# power.net
KiCad netlist of a schematic drawn in Altium Designer
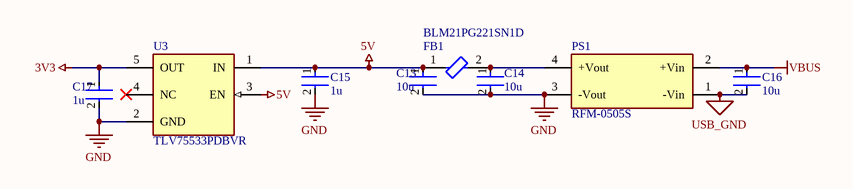
[diagram p0: power.SchDoc]

(export (version "E")
  (design (tool "Eeschema 10.0.6"))
  (components
    (comp (ref "C13")
      (value "10u")
      (footprint "C_IM 0603")
      (description "Multilayer Ceramic Capacitors MLCC – SMD/SMT; YAGEO; CC0603MRX5R7BB106; 10 µF; 0603; 16 V; 16 V")
      (fields
        (field (name "MANUFACTURER") "Yageo Group")
        (field (name "MANUFACTURER PART NUMBER") "CC0603MRX5R7BB106")
      )
      (libsource (lib "Schlib1") (part "CC0603MRX5R7BB106"))
    )
    (comp (ref "C14")
      (value "10u")
      (footprint "C_IM 0603")
      (description "Multilayer Ceramic Capacitors MLCC – SMD/SMT; YAGEO; CC0603MRX5R7BB106; 10 µF; 0603; 16 V; 16 V")
      (fields
        (field (name "MANUFACTURER") "Yageo Group")
        (field (name "MANUFACTURER PART NUMBER") "CC0603MRX5R7BB106")
      )
      (libsource (lib "Schlib1") (part "CC0603MRX5R7BB106"))
    )
    (comp (ref "C15")
      (value "1u")
      (footprint "C_IM 0603")
      (description "16V 1uF X7R ±10% 0603 Multilayer Ceramic Capacitors MLCC - SMD/SMT ROHS")
      (fields
        (field (name "MANUFACTURER") "Yageo Group")
        (field (name "MANUFACTURER PART NUMBER") "CC0603KRX7R7BB105")
      )
      (libsource (lib "Schlib1") (part "CC0603KRX7R7BB105"))
    )
    (comp (ref "C16")
      (value "10u")
      (footprint "C_IM 0603")
      (description "Multilayer Ceramic Capacitors MLCC – SMD/SMT; YAGEO; CC0603MRX5R7BB106; 10 µF; 0603; 16 V; 16 V")
      (fields
        (field (name "MANUFACTURER") "Yageo Group")
        (field (name "MANUFACTURER PART NUMBER") "CC0603MRX5R7BB106")
      )
      (libsource (lib "Schlib1") (part "CC0603MRX5R7BB106"))
    )
    (comp (ref "C17")
      (value "1u")
      (footprint "C_IM 0603")
      (description "16V 1uF X7R ±10% 0603 Multilayer Ceramic Capacitors MLCC - SMD/SMT ROHS")
      (fields
        (field (name "MANUFACTURER") "Yageo Group")
        (field (name "MANUFACTURER PART NUMBER") "CC0603KRX7R7BB105")
      )
      (libsource (lib "Schlib1") (part "CC0603KRX7R7BB105"))
    )
    (comp (ref "FB1")
      (value "BLM21PG221SN1D")
      (footprint "FB_IM 0805")
      (description "Ferrite Beads Multi-Layer 220Ohm 25% 100MHz 2A 45mOhm DCR 0805 Paper T/R")
      (fields (field (name "MANUFACTURER") "Murata") (field (name "TOLERANCE") "25%"))
      (libsource (lib "high_voltage_controller") (part "BLM21PG221SN1D"))
    )
    (comp (ref "PS1")
      (value "RFM-0505S")
      (footprint "4-SIP")
      (description "DC DC CONVERTER 5V 1W / Isolated Module DC DC Converter 1 Output 5V 200mA - 5V Input")
      (fields (field (name "MANUFACTURER") "Recom Power"))
      (libsource (lib "Schlib1") (part "RFM-0505S"))
    )
    (comp (ref "U3")
      (value "TLV75533PDBVR")
      (footprint "SOT-23-5")
      (description "500mA high-PSRR low-IQ low-dropout voltage regulator with enable 5-SOT-23 -40 to 125")
      (fields (field (name "MANUFACTURER") "Texas Instruments"))
      (libsource (lib "high_voltage_controller") (part "TLV75533PDBVR"))
    )
  )
  (nets
    (net (code "1") (name "3V3") (class "Default")
      (node (ref "C17") (pin "1") (pinfunction "1_1") (pintype "passive"))
      (node (ref "U3") (pin "5") (pinfunction "OUT_5") (pintype "power_in"))
    )
    (net (code "2") (name "5V") (class "Default")
      (node (ref "C13") (pin "1") (pinfunction "1_1") (pintype "passive"))
      (node (ref "C15") (pin "1") (pinfunction "1_1") (pintype "passive"))
      (node (ref "FB1") (pin "1") (pinfunction "1_1") (pintype "passive"))
      (node (ref "U3") (pin "1") (pinfunction "IN_1") (pintype "power_in"))
      (node (ref "U3") (pin "3") (pinfunction "EN_3") (pintype "input"))
    )
    (net (code "3") (name "GND") (class "Default")
      (node (ref "C13") (pin "2") (pinfunction "2_2") (pintype "passive"))
      (node (ref "C14") (pin "2") (pinfunction "2_2") (pintype "passive"))
      (node (ref "C15") (pin "2") (pinfunction "2_2") (pintype "passive"))
      (node (ref "C17") (pin "2") (pinfunction "2_2") (pintype "passive"))
      (node (ref "PS1") (pin "3") (pinfunction "-Vout_3") (pintype "power_in"))
      (node (ref "U3") (pin "2") (pinfunction "GND_2") (pintype "power_in"))
    )
    (net (code "4") (name "Net-(PS1-+Vout)") (class "Default")
      (node (ref "C14") (pin "1") (pinfunction "1_1") (pintype "passive"))
      (node (ref "FB1") (pin "2") (pinfunction "2_2") (pintype "passive"))
      (node (ref "PS1") (pin "4") (pinfunction "+Vout_4") (pintype "power_in"))
    )
    (net (code "5") (name "USB_GND") (class "Default")
      (node (ref "C16") (pin "2") (pinfunction "2_2") (pintype "passive"))
      (node (ref "PS1") (pin "1") (pinfunction "-Vin_1") (pintype "power_in"))
    )
    (net (code "6") (name "VBUS") (class "Default")
      (node (ref "C16") (pin "1") (pinfunction "1_1") (pintype "passive"))
      (node (ref "PS1") (pin "2") (pinfunction "+Vin_2") (pintype "power_in"))
    )
    (net (code "7") (name "unconnected-(U3-NC-Pad4)") (class "Default")
      (node (ref "U3") (pin "4") (pinfunction "NC_4") (pintype "passive+no_connect"))
    )
  )
)
